# dualevse.net
KiCad netlist of a schematic drawn in EAGLE
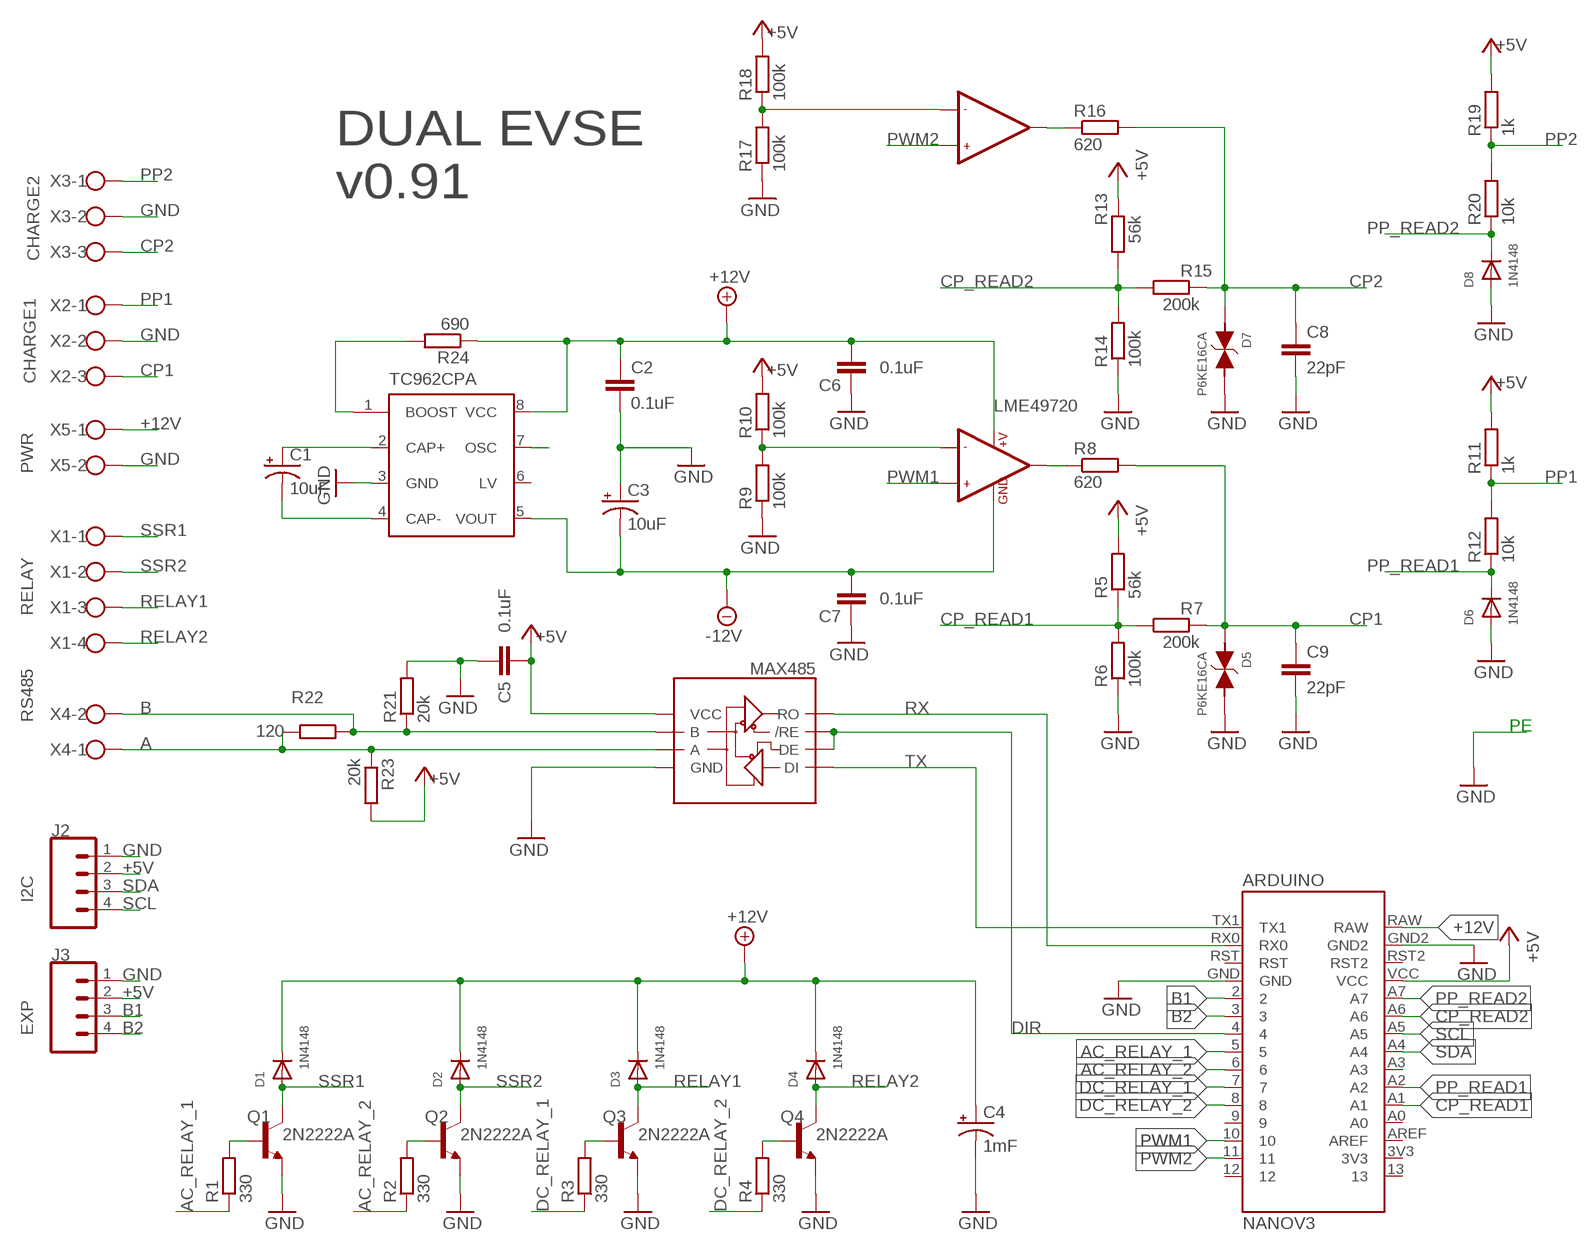
[diagram p0: schematic, sheet 1]

(export (version "E")
  (design (tool "Eeschema 10.0.6"))
  (components
    (comp (ref "ARDUINO")
      (value "NANOV3")
      (footprint "eagle-import:NANOV3")
      (libsource (lib "eagle-import") (part "NANOV3"))
    )
    (comp (ref "C1")
      (value "10uF")
      (footprint "eagle-import:CPOL-RADIAL-2.5MM-5MM")
      (libsource (lib "eagle-import") (part "10UF-POLAR-RADIAL-2.5MM-25V-20%"))
    )
    (comp (ref "C2")
      (value "0.1uF")
      (footprint "eagle-import:CAP-PTH-SMALL-KIT")
      (libsource (lib "eagle-import") (part "0.1UF-KIT-EZ-50V-20%"))
    )
    (comp (ref "C3")
      (value "10uF")
      (footprint "eagle-import:CPOL-RADIAL-2.5MM-5MM")
      (libsource (lib "eagle-import") (part "10UF-POLAR-RADIAL-2.5MM-25V-20%"))
    )
    (comp (ref "C4")
      (value "1mF")
      (footprint "eagle-import:CPOL-RADIAL-5MM-10MM")
      (libsource (lib "eagle-import") (part "1000UF-RADIAL-5MM-25V-20%"))
    )
    (comp (ref "C5")
      (value "0.1uF")
      (footprint "eagle-import:CAP-PTH-SMALL-KIT")
      (libsource (lib "eagle-import") (part "0.1UF-KIT-EZ-50V-20%"))
    )
    (comp (ref "C6")
      (value "0.1uF")
      (footprint "eagle-import:CAP-PTH-SMALL-KIT")
      (libsource (lib "eagle-import") (part "0.1UF-KIT-EZ-50V-20%"))
    )
    (comp (ref "C7")
      (value "0.1uF")
      (footprint "eagle-import:CAP-PTH-SMALL-KIT")
      (libsource (lib "eagle-import") (part "0.1UF-KIT-EZ-50V-20%"))
    )
    (comp (ref "C8")
      (value "22pF")
      (footprint "eagle-import:CAP-PTH-2.54")
      (libsource (lib "eagle-import") (part "22PF-PTH-2.54MM-200V-5%"))
    )
    (comp (ref "C9")
      (value "22pF")
      (footprint "eagle-import:CAP-PTH-2.54")
      (libsource (lib "eagle-import") (part "22PF-PTH-2.54MM-200V-5%"))
    )
    (comp (ref "D1")
      (value "1N4148")
      (footprint "eagle-import:DO-1N4148")
      (libsource (lib "eagle-import") (part "DIODEDO-1N4148"))
    )
    (comp (ref "D2")
      (value "1N4148")
      (footprint "eagle-import:DO-1N4148")
      (libsource (lib "eagle-import") (part "DIODEDO-1N4148"))
    )
    (comp (ref "D3")
      (value "1N4148")
      (footprint "eagle-import:DO-1N4148")
      (libsource (lib "eagle-import") (part "DIODEDO-1N4148"))
    )
    (comp (ref "D4")
      (value "1N4148")
      (footprint "eagle-import:DO-1N4148")
      (libsource (lib "eagle-import") (part "DIODEDO-1N4148"))
    )
    (comp (ref "D5")
      (value "P6KE16CA")
      (footprint "eagle-import:C4111-15")
      (libsource (lib "eagle-import") (part "TVSDO2"))
    )
    (comp (ref "D6")
      (value "1N4148")
      (footprint "eagle-import:DO-1N4148")
      (libsource (lib "eagle-import") (part "DIODEDO-1N4148"))
    )
    (comp (ref "D7")
      (value "P6KE16CA")
      (footprint "eagle-import:C4111-15")
      (libsource (lib "eagle-import") (part "TVSDO2"))
    )
    (comp (ref "D8")
      (value "1N4148")
      (footprint "eagle-import:DO-1N4148")
      (libsource (lib "eagle-import") (part "DIODEDO-1N4148"))
    )
    (comp (ref "J2")
      (value "I2C")
      (footprint "eagle-import:MOLEX-1X4")
      (libsource (lib "eagle-import") (part "CONN_04POLAR"))
    )
    (comp (ref "J3")
      (value "EXP")
      (footprint "eagle-import:MOLEX-1X4")
      (libsource (lib "eagle-import") (part "CONN_04POLAR"))
    )
    (comp (ref "LME49720")
      (value "LME49720")
      (footprint "eagle-import:TEXAS_DIL08")
      (libsource (lib "eagle-import") (part "LF353DIL08"))
    )
    (comp (ref "MAX485")
      (value "SPARKFUN-IC-COMMS_RS485")
      (footprint "eagle-import:TEXAS_DIL08")
      (libsource (lib "eagle-import") (part "SPARKFUN-IC-COMMS_RS485"))
    )
    (comp (ref "Q1")
      (value "2N2222A")
      (footprint "eagle-import:TO18")
      (libsource (lib "eagle-import") (part "2N2222A"))
    )
    (comp (ref "Q2")
      (value "2N2222A")
      (footprint "eagle-import:TO18")
      (libsource (lib "eagle-import") (part "2N2222A"))
    )
    (comp (ref "Q3")
      (value "2N2222A")
      (footprint "eagle-import:TO18")
      (libsource (lib "eagle-import") (part "2N2222A"))
    )
    (comp (ref "Q4")
      (value "2N2222A")
      (footprint "eagle-import:TO18")
      (libsource (lib "eagle-import") (part "2N2222A"))
    )
    (comp (ref "R1")
      (value "330")
      (footprint "eagle-import:0207_10")
      (libsource (lib "eagle-import") (part "R-EU_0207/10"))
    )
    (comp (ref "R2")
      (value "330")
      (footprint "eagle-import:0207_10")
      (libsource (lib "eagle-import") (part "R-EU_0207/10"))
    )
    (comp (ref "R3")
      (value "330")
      (footprint "eagle-import:0207_10")
      (libsource (lib "eagle-import") (part "R-EU_0207/10"))
    )
    (comp (ref "R4")
      (value "330")
      (footprint "eagle-import:0207_10")
      (libsource (lib "eagle-import") (part "R-EU_0207/10"))
    )
    (comp (ref "R5")
      (value "56k")
      (footprint "eagle-import:0207_10")
      (libsource (lib "eagle-import") (part "R-EU_0207/10"))
    )
    (comp (ref "R6")
      (value "100k")
      (footprint "eagle-import:0207_10")
      (libsource (lib "eagle-import") (part "R-EU_0207/10"))
    )
    (comp (ref "R7")
      (value "200k")
      (footprint "eagle-import:0207_10")
      (libsource (lib "eagle-import") (part "R-EU_0207/10"))
    )
    (comp (ref "R8")
      (value "620")
      (footprint "eagle-import:0207_10")
      (libsource (lib "eagle-import") (part "R-EU_0207/10"))
    )
    (comp (ref "R9")
      (value "100k")
      (footprint "eagle-import:0207_10")
      (libsource (lib "eagle-import") (part "R-EU_0207/10"))
    )
    (comp (ref "R10")
      (value "100k")
      (footprint "eagle-import:0207_10")
      (libsource (lib "eagle-import") (part "R-EU_0207/10"))
    )
    (comp (ref "R11")
      (value "1k")
      (footprint "eagle-import:0207_10")
      (libsource (lib "eagle-import") (part "R-EU_0207/10"))
    )
    (comp (ref "R12")
      (value "10k")
      (footprint "eagle-import:0207_10")
      (libsource (lib "eagle-import") (part "R-EU_0207/10"))
    )
    (comp (ref "R13")
      (value "56k")
      (footprint "eagle-import:0207_10")
      (libsource (lib "eagle-import") (part "R-EU_0207/10"))
    )
    (comp (ref "R14")
      (value "100k")
      (footprint "eagle-import:0207_10")
      (libsource (lib "eagle-import") (part "R-EU_0207/10"))
    )
    (comp (ref "R15")
      (value "200k")
      (footprint "eagle-import:0207_10")
      (libsource (lib "eagle-import") (part "R-EU_0207/10"))
    )
    (comp (ref "R16")
      (value "620")
      (footprint "eagle-import:0207_10")
      (libsource (lib "eagle-import") (part "R-EU_0207/10"))
    )
    (comp (ref "R17")
      (value "100k")
      (footprint "eagle-import:0207_10")
      (libsource (lib "eagle-import") (part "R-EU_0207/10"))
    )
    (comp (ref "R18")
      (value "100k")
      (footprint "eagle-import:0207_10")
      (libsource (lib "eagle-import") (part "R-EU_0207/10"))
    )
    (comp (ref "R19")
      (value "1k")
      (footprint "eagle-import:0207_10")
      (libsource (lib "eagle-import") (part "R-EU_0207/10"))
    )
    (comp (ref "R20")
      (value "10k")
      (footprint "eagle-import:0207_10")
      (libsource (lib "eagle-import") (part "R-EU_0207/10"))
    )
    (comp (ref "R21")
      (value "20k")
      (footprint "eagle-import:0207_10")
      (libsource (lib "eagle-import") (part "R-EU_0207/10"))
    )
    (comp (ref "R22")
      (value "120")
      (footprint "eagle-import:0207_10")
      (libsource (lib "eagle-import") (part "R-EU_0207/10"))
    )
    (comp (ref "R23")
      (value "20k")
      (footprint "eagle-import:0207_10")
      (libsource (lib "eagle-import") (part "R-EU_0207/10"))
    )
    (comp (ref "R24")
      (value "690")
      (footprint "eagle-import:0207_10")
      (libsource (lib "eagle-import") (part "R-EU_0207/10"))
    )
    (comp (ref "TC962CPA")
      (value "TEXAS_TL7660")
      (footprint "eagle-import:TEXAS_DIL08")
      (libsource (lib "eagle-import") (part "TEXAS_TL7660"))
    )
    (comp (ref "X1")
      (value "RELAY")
      (footprint "eagle-import:W237-4")
      (libsource (lib "eagle-import") (part "W237-4"))
    )
    (comp (ref "X2")
      (value "CHARGE1")
      (footprint "eagle-import:W237-103")
      (fields (field (name "MPN") "237-103"))
      (libsource (lib "eagle-import") (part "W237-103"))
    )
    (comp (ref "X3")
      (value "CHARGE2")
      (footprint "eagle-import:W237-103")
      (fields (field (name "MPN") "237-103"))
      (libsource (lib "eagle-import") (part "W237-103"))
    )
    (comp (ref "X4")
      (value "RS485")
      (footprint "eagle-import:W237-102")
      (fields (field (name "MPN") "237-102"))
      (libsource (lib "eagle-import") (part "W237-102"))
    )
    (comp (ref "X5")
      (value "PWR")
      (footprint "eagle-import:W237-102")
      (fields (field (name "MPN") "237-102"))
      (libsource (lib "eagle-import") (part "W237-102"))
    )
  )
  (nets
    (net (code "1") (name "+5V") (class "Default")
      (node (ref "ARDUINO") (pin "VCC") (pinfunction "VCC_VCC") (pintype "bidirectional"))
      (node (ref "C5") (pin "2") (pinfunction "2_2") (pintype "passive"))
      (node (ref "J2") (pin "2") (pinfunction "2_2") (pintype "passive"))
      (node (ref "J3") (pin "2") (pinfunction "2_2") (pintype "passive"))
      (node (ref "MAX485") (pin "8") (pinfunction "VCC_8") (pintype "bidirectional"))
      (node (ref "R10") (pin "2") (pinfunction "2_2") (pintype "passive"))
      (node (ref "R11") (pin "2") (pinfunction "2_2") (pintype "passive"))
      (node (ref "R13") (pin "2") (pinfunction "2_2") (pintype "passive"))
      (node (ref "R18") (pin "2") (pinfunction "2_2") (pintype "passive"))
      (node (ref "R19") (pin "2") (pinfunction "2_2") (pintype "passive"))
      (node (ref "R23") (pin "2") (pinfunction "2_2") (pintype "passive"))
      (node (ref "R5") (pin "2") (pinfunction "2_2") (pintype "passive"))
    )
    (net (code "2") (name "+12V") (class "Default")
      (node (ref "ARDUINO") (pin "RAW") (pinfunction "RAW_RAW") (pintype "bidirectional"))
      (node (ref "C2") (pin "1") (pinfunction "1_1") (pintype "passive"))
      (node (ref "C4") (pin "+") (pinfunction "+_+") (pintype "passive"))
      (node (ref "C6") (pin "1") (pinfunction "1_1") (pintype "passive"))
      (node (ref "D1") (pin "C") (pinfunction "C_C") (pintype "passive"))
      (node (ref "D2") (pin "C") (pinfunction "C_C") (pintype "passive"))
      (node (ref "D3") (pin "C") (pinfunction "C_C") (pintype "passive"))
      (node (ref "D4") (pin "C") (pinfunction "C_C") (pintype "passive"))
      (node (ref "LME49720") (pin "8") (pinfunction "+V_8") (pintype "power_in"))
      (node (ref "R24") (pin "1") (pinfunction "1_1") (pintype "passive"))
      (node (ref "TC962CPA") (pin "8") (pinfunction "VCC_8") (pintype "power_in"))
      (node (ref "X5") (pin "1") (pinfunction "KL_1") (pintype "passive"))
    )
    (net (code "3") (name "-12V") (class "Default")
      (node (ref "C3") (pin "2") (pinfunction "-_2") (pintype "passive"))
      (node (ref "C7") (pin "2") (pinfunction "2_2") (pintype "passive"))
      (node (ref "LME49720") (pin "4") (pinfunction "GND_4") (pintype "power_in"))
      (node (ref "TC962CPA") (pin "5") (pinfunction "VOUT_5") (pintype "passive"))
    )
    (net (code "4") (name "/A") (class "Default")
      (node (ref "MAX485") (pin "6") (pinfunction "A_6") (pintype "bidirectional"))
      (node (ref "R22") (pin "1") (pinfunction "1_1") (pintype "passive"))
      (node (ref "R23") (pin "1") (pinfunction "1_1") (pintype "passive"))
      (node (ref "X4") (pin "1") (pinfunction "KL_1") (pintype "passive"))
    )
    (net (code "5") (name "/B") (class "Default")
      (node (ref "MAX485") (pin "7") (pinfunction "B_7") (pintype "bidirectional"))
      (node (ref "R21") (pin "1") (pinfunction "1_1") (pintype "passive"))
      (node (ref "R22") (pin "2") (pinfunction "2_2") (pintype "passive"))
      (node (ref "X4") (pin "2") (pinfunction "KL_2") (pintype "passive"))
    )
    (net (code "6") (name "/CP1") (class "Default")
      (node (ref "C9") (pin "1") (pinfunction "1_1") (pintype "passive"))
      (node (ref "D5") (pin "A") (pinfunction "1_A") (pintype "passive"))
      (node (ref "R7") (pin "2") (pinfunction "2_2") (pintype "passive"))
      (node (ref "R8") (pin "2") (pinfunction "2_2") (pintype "passive"))
      (node (ref "X2") (pin "3") (pinfunction "KL_3") (pintype "passive"))
    )
    (net (code "7") (name "/CP2") (class "Default")
      (node (ref "C8") (pin "1") (pinfunction "1_1") (pintype "passive"))
      (node (ref "D7") (pin "A") (pinfunction "1_A") (pintype "passive"))
      (node (ref "R15") (pin "2") (pinfunction "2_2") (pintype "passive"))
      (node (ref "R16") (pin "2") (pinfunction "2_2") (pintype "passive"))
      (node (ref "X3") (pin "3") (pinfunction "KL_3") (pintype "passive"))
    )
    (net (code "8") (name "/DIR") (class "Default")
      (node (ref "ARDUINO") (pin "4") (pinfunction "4_4") (pintype "bidirectional"))
      (node (ref "MAX485") (pin "2") (pinfunction "/RE_2") (pintype "bidirectional"))
      (node (ref "MAX485") (pin "3") (pinfunction "DE_3") (pintype "bidirectional"))
    )
    (net (code "9") (name "/PP1") (class "Default")
      (node (ref "R11") (pin "1") (pinfunction "1_1") (pintype "passive"))
      (node (ref "R12") (pin "2") (pinfunction "2_2") (pintype "passive"))
      (node (ref "X2") (pin "1") (pinfunction "KL_1") (pintype "passive"))
    )
    (net (code "10") (name "/PP2") (class "Default")
      (node (ref "R19") (pin "1") (pinfunction "1_1") (pintype "passive"))
      (node (ref "R20") (pin "2") (pinfunction "2_2") (pintype "passive"))
      (node (ref "X3") (pin "1") (pinfunction "KL_1") (pintype "passive"))
    )
    (net (code "11") (name "/RELAY1") (class "Default")
      (node (ref "D3") (pin "A") (pinfunction "A_A") (pintype "passive"))
      (node (ref "Q3") (pin "3") (pinfunction "C_3") (pintype "passive"))
      (node (ref "X1") (pin "3") (pinfunction "KL_3") (pintype "passive"))
    )
    (net (code "12") (name "/RELAY2") (class "Default")
      (node (ref "D4") (pin "A") (pinfunction "A_A") (pintype "passive"))
      (node (ref "Q4") (pin "3") (pinfunction "C_3") (pintype "passive"))
      (node (ref "X1") (pin "4") (pinfunction "KL_4") (pintype "passive"))
    )
    (net (code "13") (name "/RX") (class "Default")
      (node (ref "ARDUINO") (pin "RX0") (pinfunction "RX0_RX0") (pintype "bidirectional"))
      (node (ref "MAX485") (pin "1") (pinfunction "RO_1") (pintype "bidirectional"))
    )
    (net (code "14") (name "/SSR1") (class "Default")
      (node (ref "D1") (pin "A") (pinfunction "A_A") (pintype "passive"))
      (node (ref "Q1") (pin "3") (pinfunction "C_3") (pintype "passive"))
      (node (ref "X1") (pin "1") (pinfunction "KL_1") (pintype "passive"))
    )
    (net (code "15") (name "/SSR2") (class "Default")
      (node (ref "D2") (pin "A") (pinfunction "A_A") (pintype "passive"))
      (node (ref "Q2") (pin "3") (pinfunction "C_3") (pintype "passive"))
      (node (ref "X1") (pin "2") (pinfunction "KL_2") (pintype "passive"))
    )
    (net (code "16") (name "/TX") (class "Default")
      (node (ref "ARDUINO") (pin "TX1") (pinfunction "TX1_TX1") (pintype "bidirectional"))
      (node (ref "MAX485") (pin "4") (pinfunction "DI_4") (pintype "bidirectional"))
    )
    (net (code "17") (name "AC_RELAY_1") (class "Default")
      (node (ref "ARDUINO") (pin "5") (pinfunction "5_5") (pintype "bidirectional"))
      (node (ref "R1") (pin "1") (pinfunction "1_1") (pintype "passive"))
    )
    (net (code "18") (name "AC_RELAY_2") (class "Default")
      (node (ref "ARDUINO") (pin "6") (pinfunction "6_6") (pintype "bidirectional"))
      (node (ref "R2") (pin "1") (pinfunction "1_1") (pintype "passive"))
    )
    (net (code "19") (name "B1") (class "Default")
      (node (ref "ARDUINO") (pin "2") (pinfunction "2_2") (pintype "bidirectional"))
      (node (ref "J3") (pin "3") (pinfunction "3_3") (pintype "passive"))
    )
    (net (code "20") (name "B2") (class "Default")
      (node (ref "ARDUINO") (pin "3") (pinfunction "3_3") (pintype "bidirectional"))
      (node (ref "J3") (pin "4") (pinfunction "4_4") (pintype "passive"))
    )
    (net (code "21") (name "CP_READ1") (class "Default")
      (node (ref "ARDUINO") (pin "A1") (pinfunction "A1_A1") (pintype "bidirectional"))
      (node (ref "R5") (pin "1") (pinfunction "1_1") (pintype "passive"))
      (node (ref "R6") (pin "2") (pinfunction "2_2") (pintype "passive"))
      (node (ref "R7") (pin "1") (pinfunction "1_1") (pintype "passive"))
    )
    (net (code "22") (name "CP_READ2") (class "Default")
      (node (ref "ARDUINO") (pin "A6") (pinfunction "A6_A6") (pintype "bidirectional"))
      (node (ref "R13") (pin "1") (pinfunction "1_1") (pintype "passive"))
      (node (ref "R14") (pin "2") (pinfunction "2_2") (pintype "passive"))
      (node (ref "R15") (pin "1") (pinfunction "1_1") (pintype "passive"))
    )
    (net (code "23") (name "DC_RELAY_1") (class "Default")
      (node (ref "ARDUINO") (pin "7") (pinfunction "7_7") (pintype "bidirectional"))
      (node (ref "R3") (pin "1") (pinfunction "1_1") (pintype "passive"))
    )
    (net (code "24") (name "DC_RELAY_2") (class "Default")
      (node (ref "ARDUINO") (pin "8") (pinfunction "8_8") (pintype "bidirectional"))
      (node (ref "R4") (pin "1") (pinfunction "1_1") (pintype "passive"))
    )
    (net (code "25") (name "GND") (class "Default")
      (node (ref "ARDUINO") (pin "GND") (pinfunction "GND_GND") (pintype "bidirectional"))
      (node (ref "ARDUINO") (pin "GND2") (pinfunction "GND2_GND2") (pintype "bidirectional"))
      (node (ref "C2") (pin "2") (pinfunction "2_2") (pintype "passive"))
      (node (ref "C3") (pin "1") (pinfunction "+_1") (pintype "passive"))
      (node (ref "C4") (pin "-") (pinfunction "-_-") (pintype "passive"))
      (node (ref "C5") (pin "1") (pinfunction "1_1") (pintype "passive"))
      (node (ref "C6") (pin "2") (pinfunction "2_2") (pintype "passive"))
      (node (ref "C7") (pin "1") (pinfunction "1_1") (pintype "passive"))
      (node (ref "C8") (pin "2") (pinfunction "2_2") (pintype "passive"))
      (node (ref "C9") (pin "2") (pinfunction "2_2") (pintype "passive"))
      (node (ref "D5") (pin "C") (pinfunction "2_C") (pintype "passive"))
      (node (ref "D6") (pin "A") (pinfunction "A_A") (pintype "passive"))
      (node (ref "D7") (pin "C") (pinfunction "2_C") (pintype "passive"))
      (node (ref "D8") (pin "A") (pinfunction "A_A") (pintype "passive"))
      (node (ref "J2") (pin "1") (pinfunction "1_1") (pintype "passive"))
      (node (ref "J3") (pin "1") (pinfunction "1_1") (pintype "passive"))
      (node (ref "MAX485") (pin "5") (pinfunction "GND_5") (pintype "bidirectional"))
      (node (ref "Q1") (pin "1") (pinfunction "E_1") (pintype "passive"))
      (node (ref "Q2") (pin "1") (pinfunction "E_1") (pintype "passive"))
      (node (ref "Q3") (pin "1") (pinfunction "E_1") (pintype "passive"))
      (node (ref "Q4") (pin "1") (pinfunction "E_1") (pintype "passive"))
      (node (ref "R14") (pin "1") (pinfunction "1_1") (pintype "passive"))
      (node (ref "R17") (pin "1") (pinfunction "1_1") (pintype "passive"))
      (node (ref "R21") (pin "2") (pinfunction "2_2") (pintype "passive"))
      (node (ref "R6") (pin "1") (pinfunction "1_1") (pintype "passive"))
      (node (ref "R9") (pin "1") (pinfunction "1_1") (pintype "passive"))
      (node (ref "TC962CPA") (pin "3") (pinfunction "GND_3") (pintype "power_in"))
      (node (ref "X2") (pin "2") (pinfunction "KL_2") (pintype "passive"))
      (node (ref "X3") (pin "2") (pinfunction "KL_2") (pintype "passive"))
      (node (ref "X5") (pin "2") (pinfunction "KL_2") (pintype "passive"))
    )
    (net (code "26") (name "Net-(C1-+)") (class "Default")
      (node (ref "C1") (pin "1") (pinfunction "+_1") (pintype "passive"))
      (node (ref "TC962CPA") (pin "2") (pinfunction "CAP+_2") (pintype "passive"))
    )
    (net (code "27") (name "Net-(C1--)") (class "Default")
      (node (ref "C1") (pin "2") (pinfunction "-_2") (pintype "passive"))
      (node (ref "TC962CPA") (pin "4") (pinfunction "CAP-_4") (pintype "passive"))
    )
    (net (code "28") (name "Net-(LME49720A--IN1)") (class "Default")
      (node (ref "LME49720") (pin "2") (pinfunction "-IN1_2") (pintype "input"))
      (node (ref "R10") (pin "1") (pinfunction "1_1") (pintype "passive"))
      (node (ref "R9") (pin "2") (pinfunction "2_2") (pintype "passive"))
    )
    (net (code "29") (name "Net-(LME49720A-OUT1)") (class "Default")
      (node (ref "LME49720") (pin "1") (pinfunction "OUT1_1") (pintype "output"))
      (node (ref "R8") (pin "1") (pinfunction "1_1") (pintype "passive"))
    )
    (net (code "30") (name "Net-(LME49720B--IN2)") (class "Default")
      (node (ref "LME49720") (pin "6") (pinfunction "-IN2_6") (pintype "input"))
      (node (ref "R17") (pin "2") (pinfunction "2_2") (pintype "passive"))
      (node (ref "R18") (pin "1") (pinfunction "1_1") (pintype "passive"))
    )
    (net (code "31") (name "Net-(LME49720B-OUT2)") (class "Default")
      (node (ref "LME49720") (pin "7") (pinfunction "OUT2_7") (pintype "output"))
      (node (ref "R16") (pin "1") (pinfunction "1_1") (pintype "passive"))
    )
    (net (code "32") (name "Net-(Q1-B)") (class "Default")
      (node (ref "Q1") (pin "2") (pinfunction "B_2") (pintype "passive"))
      (node (ref "R1") (pin "2") (pinfunction "2_2") (pintype "passive"))
    )
    (net (code "33") (name "Net-(Q2-B)") (class "Default")
      (node (ref "Q2") (pin "2") (pinfunction "B_2") (pintype "passive"))
      (node (ref "R2") (pin "2") (pinfunction "2_2") (pintype "passive"))
    )
    (net (code "34") (name "Net-(Q3-B)") (class "Default")
      (node (ref "Q3") (pin "2") (pinfunction "B_2") (pintype "passive"))
      (node (ref "R3") (pin "2") (pinfunction "2_2") (pintype "passive"))
    )
    (net (code "35") (name "Net-(Q4-B)") (class "Default")
      (node (ref "Q4") (pin "2") (pinfunction "B_2") (pintype "passive"))
      (node (ref "R4") (pin "2") (pinfunction "2_2") (pintype "passive"))
    )
    (net (code "36") (name "Net-(TC962CPA-BOOST)") (class "Default")
      (node (ref "R24") (pin "2") (pinfunction "2_2") (pintype "passive"))
      (node (ref "TC962CPA") (pin "1") (pinfunction "BOOST_1") (pintype "bidirectional"))
    )
    (net (code "37") (name "PP_READ1") (class "Default")
      (node (ref "ARDUINO") (pin "A2") (pinfunction "A2_A2") (pintype "bidirectional"))
      (node (ref "D6") (pin "C") (pinfunction "C_C") (pintype "passive"))
      (node (ref "R12") (pin "1") (pinfunction "1_1") (pintype "passive"))
    )
    (net (code "38") (name "PP_READ2") (class "Default")
      (node (ref "ARDUINO") (pin "A7") (pinfunction "A7_A7") (pintype "bidirectional"))
      (node (ref "D8") (pin "C") (pinfunction "C_C") (pintype "passive"))
      (node (ref "R20") (pin "1") (pinfunction "1_1") (pintype "passive"))
    )
    (net (code "39") (name "PWM1") (class "Default")
      (node (ref "ARDUINO") (pin "10") (pinfunction "10_10") (pintype "bidirectional"))
      (node (ref "LME49720") (pin "3") (pinfunction "+IN1_3") (pintype "input"))
    )
    (net (code "40") (name "PWM2") (class "Default")
      (node (ref "ARDUINO") (pin "11") (pinfunction "11_11") (pintype "bidirectional"))
      (node (ref "LME49720") (pin "5") (pinfunction "+IN2_5") (pintype "input"))
    )
    (net (code "41") (name "SCL") (class "Default")
      (node (ref "ARDUINO") (pin "A5") (pinfunction "A5_A5") (pintype "bidirectional"))
      (node (ref "J2") (pin "4") (pinfunction "4_4") (pintype "passive"))
    )
    (net (code "42") (name "SDA") (class "Default")
      (node (ref "ARDUINO") (pin "A4") (pinfunction "A4_A4") (pintype "bidirectional"))
      (node (ref "J2") (pin "3") (pinfunction "3_3") (pintype "passive"))
    )
    (net (code "43") (name "unconnected-(ARDUINO-Pad3V3)") (class "Default")
      (node (ref "ARDUINO") (pin "3V3") (pinfunction "3V3_3V3") (pintype "bidirectional"))
    )
    (net (code "44") (name "unconnected-(ARDUINO-Pad9)") (class "Default")
      (node (ref "ARDUINO") (pin "9") (pinfunction "9_9") (pintype "bidirectional"))
    )
    (net (code "45") (name "unconnected-(ARDUINO-Pad12)") (class "Default")
      (node (ref "ARDUINO") (pin "12") (pinfunction "12_12") (pintype "bidirectional"))
    )
    (net (code "46") (name "unconnected-(ARDUINO-Pad13)") (class "Default")
      (node (ref "ARDUINO") (pin "13") (pinfunction "13_13") (pintype "bidirectional"))
    )
    (net (code "47") (name "unconnected-(ARDUINO-PadA0)") (class "Default")
      (node (ref "ARDUINO") (pin "A0") (pinfunction "A0_A0") (pintype "bidirectional"))
    )
    (net (code "48") (name "unconnected-(ARDUINO-PadA3)") (class "Default")
      (node (ref "ARDUINO") (pin "A3") (pinfunction "A3_A3") (pintype "bidirectional"))
    )
    (net (code "49") (name "unconnected-(ARDUINO-PadAREF)") (class "Default")
      (node (ref "ARDUINO") (pin "AREF") (pinfunction "AREF_AREF") (pintype "bidirectional"))
    )
    (net (code "50") (name "unconnected-(ARDUINO-PadRST)") (class "Default")
      (node (ref "ARDUINO") (pin "RST") (pinfunction "RST_RST") (pintype "bidirectional"))
    )
    (net (code "51") (name "unconnected-(ARDUINO-PadRST2)") (class "Default")
      (node (ref "ARDUINO") (pin "RST2") (pinfunction "RST2_RST2") (pintype "bidirectional"))
    )
    (net (code "52") (name "unconnected-(TC962CPA-LV-Pad6)") (class "Default")
      (node (ref "TC962CPA") (pin "6") (pinfunction "LV_6") (pintype "passive"))
    )
    (net (code "53") (name "unconnected-(TC962CPA-OSC-Pad7)") (class "Default")
      (node (ref "TC962CPA") (pin "7") (pinfunction "OSC_7") (pintype "input"))
    )
  )
)
